# LED_Matrix.net
KiCad netlist of a schematic drawn in EAGLE
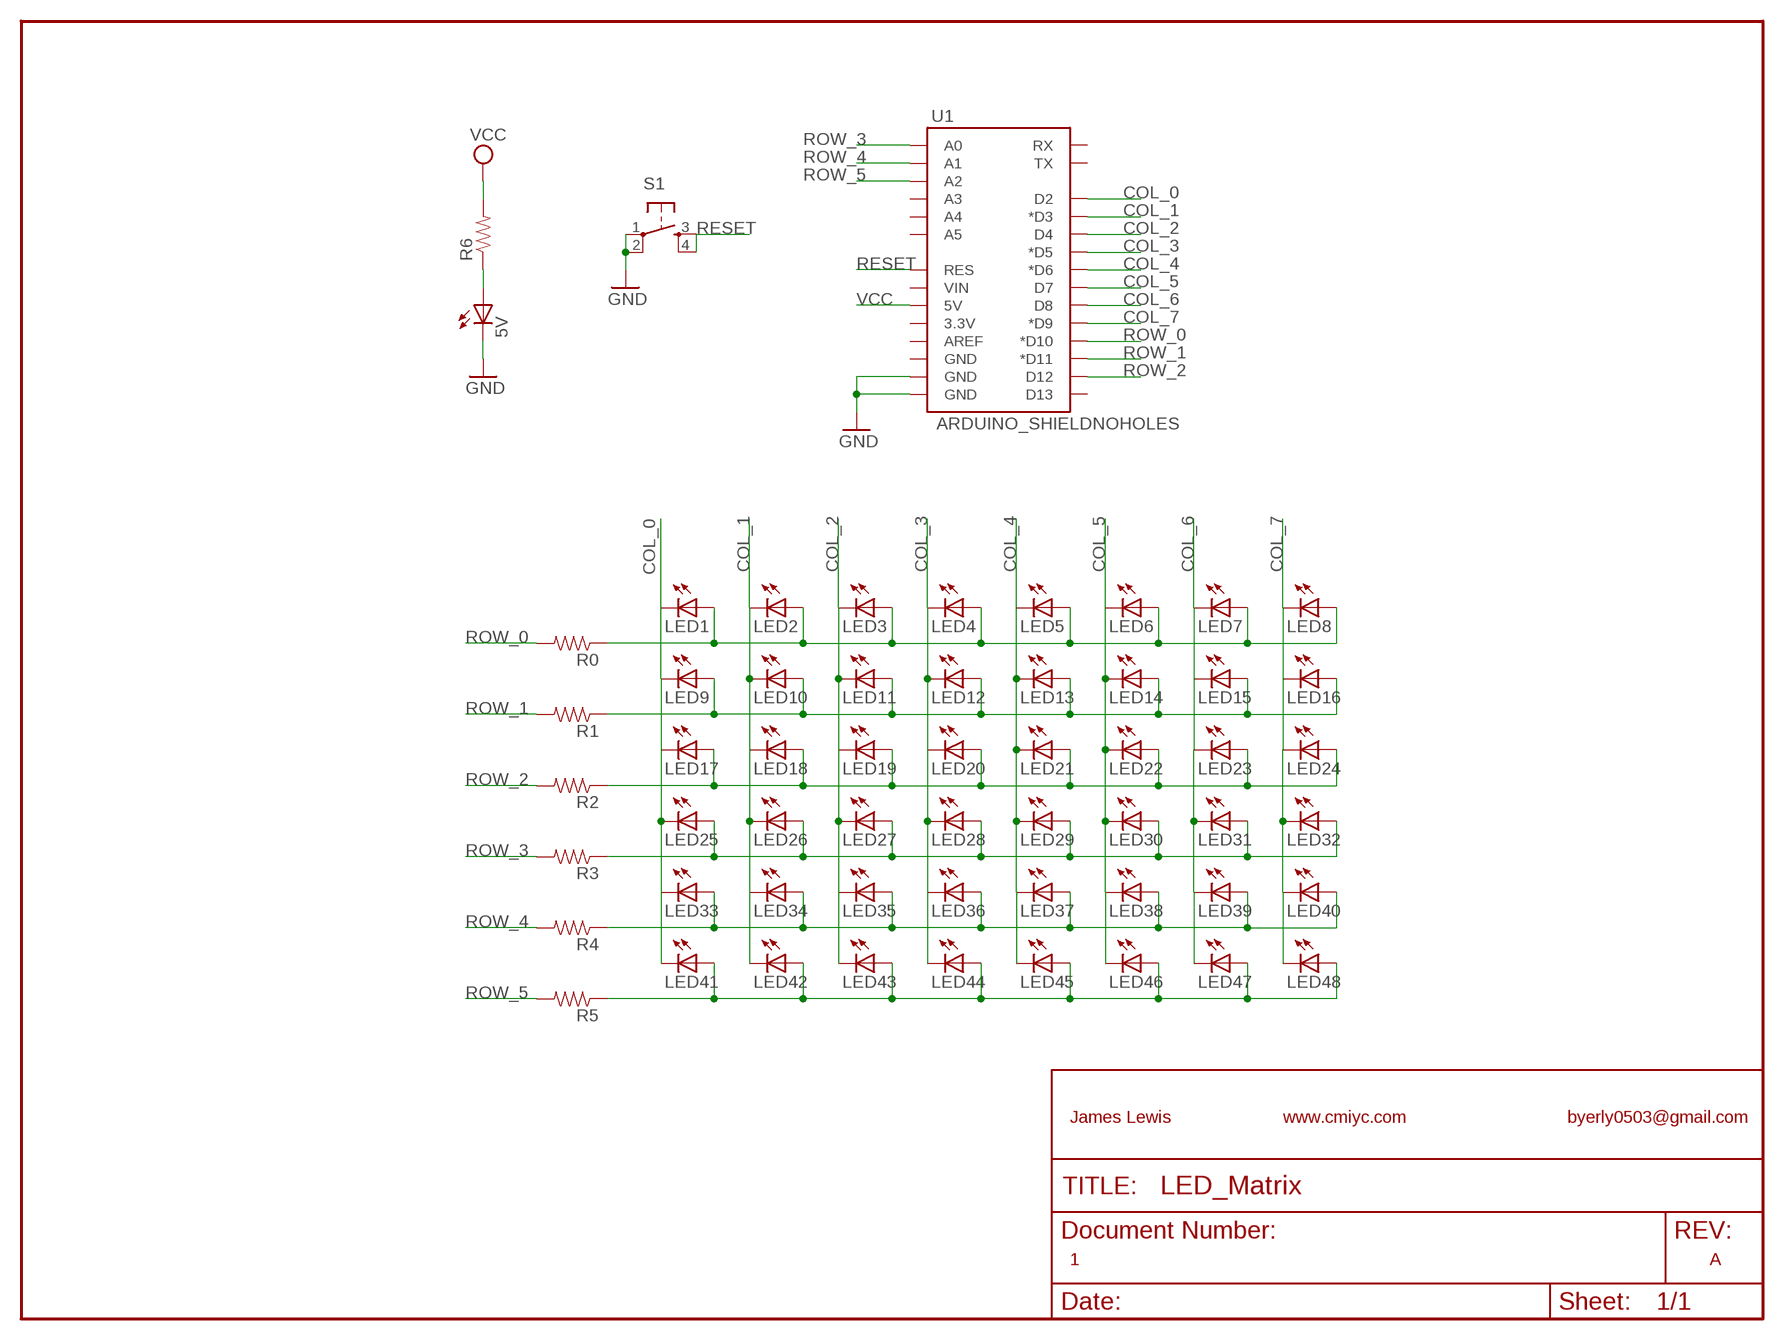
[diagram p0: schematic, sheet 1]

(export (version "E")
  (design (tool "Eeschema 10.0.6"))
  (components
    (comp (ref "5V")
      (value "LED1206")
      (footprint "eagle-import:LED-1206")
      (libsource (lib "eagle-import") (part "LED1206"))
    )
    (comp (ref "LED1")
      (value "LED5MM")
      (footprint "eagle-import:LED5MM")
      (libsource (lib "eagle-import") (part "LED5MM"))
    )
    (comp (ref "LED2")
      (value "LED5MM")
      (footprint "eagle-import:LED5MM")
      (libsource (lib "eagle-import") (part "LED5MM"))
    )
    (comp (ref "LED3")
      (value "LED5MM")
      (footprint "eagle-import:LED5MM")
      (libsource (lib "eagle-import") (part "LED5MM"))
    )
    (comp (ref "LED4")
      (value "LED5MM")
      (footprint "eagle-import:LED5MM")
      (libsource (lib "eagle-import") (part "LED5MM"))
    )
    (comp (ref "LED5")
      (value "LED5MM")
      (footprint "eagle-import:LED5MM")
      (libsource (lib "eagle-import") (part "LED5MM"))
    )
    (comp (ref "LED6")
      (value "LED5MM")
      (footprint "eagle-import:LED5MM")
      (libsource (lib "eagle-import") (part "LED5MM"))
    )
    (comp (ref "LED7")
      (value "LED5MM")
      (footprint "eagle-import:LED5MM")
      (libsource (lib "eagle-import") (part "LED5MM"))
    )
    (comp (ref "LED8")
      (value "LED5MM")
      (footprint "eagle-import:LED5MM")
      (libsource (lib "eagle-import") (part "LED5MM"))
    )
    (comp (ref "LED9")
      (value "LED5MM")
      (footprint "eagle-import:LED5MM")
      (libsource (lib "eagle-import") (part "LED5MM"))
    )
    (comp (ref "LED10")
      (value "LED5MM")
      (footprint "eagle-import:LED5MM")
      (libsource (lib "eagle-import") (part "LED5MM"))
    )
    (comp (ref "LED11")
      (value "LED5MM")
      (footprint "eagle-import:LED5MM")
      (libsource (lib "eagle-import") (part "LED5MM"))
    )
    (comp (ref "LED12")
      (value "LED5MM")
      (footprint "eagle-import:LED5MM")
      (libsource (lib "eagle-import") (part "LED5MM"))
    )
    (comp (ref "LED13")
      (value "LED5MM")
      (footprint "eagle-import:LED5MM")
      (libsource (lib "eagle-import") (part "LED5MM"))
    )
    (comp (ref "LED14")
      (value "LED5MM")
      (footprint "eagle-import:LED5MM")
      (libsource (lib "eagle-import") (part "LED5MM"))
    )
    (comp (ref "LED15")
      (value "LED5MM")
      (footprint "eagle-import:LED5MM")
      (libsource (lib "eagle-import") (part "LED5MM"))
    )
    (comp (ref "LED16")
      (value "LED5MM")
      (footprint "eagle-import:LED5MM")
      (libsource (lib "eagle-import") (part "LED5MM"))
    )
    (comp (ref "LED17")
      (value "LED5MM")
      (footprint "eagle-import:LED5MM")
      (libsource (lib "eagle-import") (part "LED5MM"))
    )
    (comp (ref "LED18")
      (value "LED5MM")
      (footprint "eagle-import:LED5MM")
      (libsource (lib "eagle-import") (part "LED5MM"))
    )
    (comp (ref "LED19")
      (value "LED5MM")
      (footprint "eagle-import:LED5MM")
      (libsource (lib "eagle-import") (part "LED5MM"))
    )
    (comp (ref "LED20")
      (value "LED5MM")
      (footprint "eagle-import:LED5MM")
      (libsource (lib "eagle-import") (part "LED5MM"))
    )
    (comp (ref "LED21")
      (value "LED5MM")
      (footprint "eagle-import:LED5MM")
      (libsource (lib "eagle-import") (part "LED5MM"))
    )
    (comp (ref "LED22")
      (value "LED5MM")
      (footprint "eagle-import:LED5MM")
      (libsource (lib "eagle-import") (part "LED5MM"))
    )
    (comp (ref "LED23")
      (value "LED5MM")
      (footprint "eagle-import:LED5MM")
      (libsource (lib "eagle-import") (part "LED5MM"))
    )
    (comp (ref "LED24")
      (value "LED5MM")
      (footprint "eagle-import:LED5MM")
      (libsource (lib "eagle-import") (part "LED5MM"))
    )
    (comp (ref "LED25")
      (value "LED5MM")
      (footprint "eagle-import:LED5MM")
      (libsource (lib "eagle-import") (part "LED5MM"))
    )
    (comp (ref "LED26")
      (value "LED5MM")
      (footprint "eagle-import:LED5MM")
      (libsource (lib "eagle-import") (part "LED5MM"))
    )
    (comp (ref "LED27")
      (value "LED5MM")
      (footprint "eagle-import:LED5MM")
      (libsource (lib "eagle-import") (part "LED5MM"))
    )
    (comp (ref "LED28")
      (value "LED5MM")
      (footprint "eagle-import:LED5MM")
      (libsource (lib "eagle-import") (part "LED5MM"))
    )
    (comp (ref "LED29")
      (value "LED5MM")
      (footprint "eagle-import:LED5MM")
      (libsource (lib "eagle-import") (part "LED5MM"))
    )
    (comp (ref "LED30")
      (value "LED5MM")
      (footprint "eagle-import:LED5MM")
      (libsource (lib "eagle-import") (part "LED5MM"))
    )
    (comp (ref "LED31")
      (value "LED5MM")
      (footprint "eagle-import:LED5MM")
      (libsource (lib "eagle-import") (part "LED5MM"))
    )
    (comp (ref "LED32")
      (value "LED5MM")
      (footprint "eagle-import:LED5MM")
      (libsource (lib "eagle-import") (part "LED5MM"))
    )
    (comp (ref "LED33")
      (value "LED5MM")
      (footprint "eagle-import:LED5MM")
      (libsource (lib "eagle-import") (part "LED5MM"))
    )
    (comp (ref "LED34")
      (value "LED5MM")
      (footprint "eagle-import:LED5MM")
      (libsource (lib "eagle-import") (part "LED5MM"))
    )
    (comp (ref "LED35")
      (value "LED5MM")
      (footprint "eagle-import:LED5MM")
      (libsource (lib "eagle-import") (part "LED5MM"))
    )
    (comp (ref "LED36")
      (value "LED5MM")
      (footprint "eagle-import:LED5MM")
      (libsource (lib "eagle-import") (part "LED5MM"))
    )
    (comp (ref "LED37")
      (value "LED5MM")
      (footprint "eagle-import:LED5MM")
      (libsource (lib "eagle-import") (part "LED5MM"))
    )
    (comp (ref "LED38")
      (value "LED5MM")
      (footprint "eagle-import:LED5MM")
      (libsource (lib "eagle-import") (part "LED5MM"))
    )
    (comp (ref "LED39")
      (value "LED5MM")
      (footprint "eagle-import:LED5MM")
      (libsource (lib "eagle-import") (part "LED5MM"))
    )
    (comp (ref "LED40")
      (value "LED5MM")
      (footprint "eagle-import:LED5MM")
      (libsource (lib "eagle-import") (part "LED5MM"))
    )
    (comp (ref "LED41")
      (value "LED5MM")
      (footprint "eagle-import:LED5MM")
      (libsource (lib "eagle-import") (part "LED5MM"))
    )
    (comp (ref "LED42")
      (value "LED5MM")
      (footprint "eagle-import:LED5MM")
      (libsource (lib "eagle-import") (part "LED5MM"))
    )
    (comp (ref "LED43")
      (value "LED5MM")
      (footprint "eagle-import:LED5MM")
      (libsource (lib "eagle-import") (part "LED5MM"))
    )
    (comp (ref "LED44")
      (value "LED5MM")
      (footprint "eagle-import:LED5MM")
      (libsource (lib "eagle-import") (part "LED5MM"))
    )
    (comp (ref "LED45")
      (value "LED5MM")
      (footprint "eagle-import:LED5MM")
      (libsource (lib "eagle-import") (part "LED5MM"))
    )
    (comp (ref "LED46")
      (value "LED5MM")
      (footprint "eagle-import:LED5MM")
      (libsource (lib "eagle-import") (part "LED5MM"))
    )
    (comp (ref "LED47")
      (value "LED5MM")
      (footprint "eagle-import:LED5MM")
      (libsource (lib "eagle-import") (part "LED5MM"))
    )
    (comp (ref "LED48")
      (value "LED5MM")
      (footprint "eagle-import:LED5MM")
      (libsource (lib "eagle-import") (part "LED5MM"))
    )
    (comp (ref "R0")
      (value "RESISTOR1206")
      (footprint "eagle-import:1206")
      (libsource (lib "eagle-import") (part "RESISTOR1206"))
    )
    (comp (ref "R1")
      (value "RESISTOR1206")
      (footprint "eagle-import:1206")
      (libsource (lib "eagle-import") (part "RESISTOR1206"))
    )
    (comp (ref "R2")
      (value "RESISTOR1206")
      (footprint "eagle-import:1206")
      (libsource (lib "eagle-import") (part "RESISTOR1206"))
    )
    (comp (ref "R3")
      (value "RESISTOR1206")
      (footprint "eagle-import:1206")
      (libsource (lib "eagle-import") (part "RESISTOR1206"))
    )
    (comp (ref "R4")
      (value "RESISTOR1206")
      (footprint "eagle-import:1206")
      (libsource (lib "eagle-import") (part "RESISTOR1206"))
    )
    (comp (ref "R5")
      (value "RESISTOR1206")
      (footprint "eagle-import:1206")
      (libsource (lib "eagle-import") (part "RESISTOR1206"))
    )
    (comp (ref "R6")
      (value "RESISTOR1206")
      (footprint "eagle-import:1206")
      (libsource (lib "eagle-import") (part "RESISTOR1206"))
    )
    (comp (ref "S1")
      (value "TAC_SWITCHSMD")
      (footprint "eagle-import:TACTILE_SWITCH_SMD")
      (libsource (lib "eagle-import") (part "TAC_SWITCHSMD"))
    )
    (comp (ref "U1")
      (value "ARDUINO_SHIELDNOHOLES")
      (footprint "eagle-import:DUEMILANOVE_SHIELD_NOHOLES")
      (libsource (lib "eagle-import") (part "ARDUINO_SHIELDNOHOLES"))
    )
  )
  (nets
    (net (code "1") (name "/COL_0") (class "Default")
      (node (ref "LED1") (pin "K") (pinfunction "C_K") (pintype "passive"))
      (node (ref "LED17") (pin "K") (pinfunction "C_K") (pintype "passive"))
      (node (ref "LED25") (pin "K") (pinfunction "C_K") (pintype "passive"))
      (node (ref "LED33") (pin "K") (pinfunction "C_K") (pintype "passive"))
      (node (ref "LED41") (pin "K") (pinfunction "C_K") (pintype "passive"))
      (node (ref "LED9") (pin "K") (pinfunction "C_K") (pintype "passive"))
      (node (ref "U1") (pin "D2") (pinfunction "D2_D2") (pintype "bidirectional"))
    )
    (net (code "2") (name "/COL_1") (class "Default")
      (node (ref "LED10") (pin "K") (pinfunction "C_K") (pintype "passive"))
      (node (ref "LED18") (pin "K") (pinfunction "C_K") (pintype "passive"))
      (node (ref "LED2") (pin "K") (pinfunction "C_K") (pintype "passive"))
      (node (ref "LED26") (pin "K") (pinfunction "C_K") (pintype "passive"))
      (node (ref "LED34") (pin "K") (pinfunction "C_K") (pintype "passive"))
      (node (ref "LED42") (pin "K") (pinfunction "C_K") (pintype "passive"))
      (node (ref "U1") (pin "D3") (pinfunction "*D3_D3") (pintype "bidirectional"))
    )
    (net (code "3") (name "/COL_2") (class "Default")
      (node (ref "LED11") (pin "K") (pinfunction "C_K") (pintype "passive"))
      (node (ref "LED19") (pin "K") (pinfunction "C_K") (pintype "passive"))
      (node (ref "LED27") (pin "K") (pinfunction "C_K") (pintype "passive"))
      (node (ref "LED3") (pin "K") (pinfunction "C_K") (pintype "passive"))
      (node (ref "LED35") (pin "K") (pinfunction "C_K") (pintype "passive"))
      (node (ref "LED43") (pin "K") (pinfunction "C_K") (pintype "passive"))
      (node (ref "U1") (pin "D4") (pinfunction "D4_D4") (pintype "bidirectional"))
    )
    (net (code "4") (name "/COL_3") (class "Default")
      (node (ref "LED12") (pin "K") (pinfunction "C_K") (pintype "passive"))
      (node (ref "LED20") (pin "K") (pinfunction "C_K") (pintype "passive"))
      (node (ref "LED28") (pin "K") (pinfunction "C_K") (pintype "passive"))
      (node (ref "LED36") (pin "K") (pinfunction "C_K") (pintype "passive"))
      (node (ref "LED4") (pin "K") (pinfunction "C_K") (pintype "passive"))
      (node (ref "LED44") (pin "K") (pinfunction "C_K") (pintype "passive"))
      (node (ref "U1") (pin "D5") (pinfunction "*D5_D5") (pintype "bidirectional"))
    )
    (net (code "5") (name "/COL_4") (class "Default")
      (node (ref "LED13") (pin "K") (pinfunction "C_K") (pintype "passive"))
      (node (ref "LED21") (pin "K") (pinfunction "C_K") (pintype "passive"))
      (node (ref "LED29") (pin "K") (pinfunction "C_K") (pintype "passive"))
      (node (ref "LED37") (pin "K") (pinfunction "C_K") (pintype "passive"))
      (node (ref "LED45") (pin "K") (pinfunction "C_K") (pintype "passive"))
      (node (ref "LED5") (pin "K") (pinfunction "C_K") (pintype "passive"))
      (node (ref "U1") (pin "D6") (pinfunction "*D6_D6") (pintype "bidirectional"))
    )
    (net (code "6") (name "/COL_5") (class "Default")
      (node (ref "LED14") (pin "K") (pinfunction "C_K") (pintype "passive"))
      (node (ref "LED22") (pin "K") (pinfunction "C_K") (pintype "passive"))
      (node (ref "LED30") (pin "K") (pinfunction "C_K") (pintype "passive"))
      (node (ref "LED38") (pin "K") (pinfunction "C_K") (pintype "passive"))
      (node (ref "LED46") (pin "K") (pinfunction "C_K") (pintype "passive"))
      (node (ref "LED6") (pin "K") (pinfunction "C_K") (pintype "passive"))
      (node (ref "U1") (pin "D7") (pinfunction "D7_D7") (pintype "bidirectional"))
    )
    (net (code "7") (name "/COL_6") (class "Default")
      (node (ref "LED15") (pin "K") (pinfunction "C_K") (pintype "passive"))
      (node (ref "LED23") (pin "K") (pinfunction "C_K") (pintype "passive"))
      (node (ref "LED31") (pin "K") (pinfunction "C_K") (pintype "passive"))
      (node (ref "LED39") (pin "K") (pinfunction "C_K") (pintype "passive"))
      (node (ref "LED47") (pin "K") (pinfunction "C_K") (pintype "passive"))
      (node (ref "LED7") (pin "K") (pinfunction "C_K") (pintype "passive"))
      (node (ref "U1") (pin "D8") (pinfunction "D8_D8") (pintype "bidirectional"))
    )
    (net (code "8") (name "/COL_7") (class "Default")
      (node (ref "LED16") (pin "K") (pinfunction "C_K") (pintype "passive"))
      (node (ref "LED24") (pin "K") (pinfunction "C_K") (pintype "passive"))
      (node (ref "LED32") (pin "K") (pinfunction "C_K") (pintype "passive"))
      (node (ref "LED40") (pin "K") (pinfunction "C_K") (pintype "passive"))
      (node (ref "LED48") (pin "K") (pinfunction "C_K") (pintype "passive"))
      (node (ref "LED8") (pin "K") (pinfunction "C_K") (pintype "passive"))
      (node (ref "U1") (pin "D9") (pinfunction "*D9_D9") (pintype "bidirectional"))
    )
    (net (code "9") (name "/RESET") (class "Default")
      (node (ref "S1") (pin "3") (pinfunction "3_3") (pintype "passive"))
      (node (ref "S1") (pin "4") (pinfunction "4_4") (pintype "passive"))
      (node (ref "U1") (pin "RES") (pinfunction "RES_RES") (pintype "bidirectional"))
    )
    (net (code "10") (name "/ROW_0") (class "Default")
      (node (ref "R0") (pin "2") (pinfunction "2_2") (pintype "passive"))
      (node (ref "U1") (pin "D10") (pinfunction "*D10_D10") (pintype "bidirectional"))
    )
    (net (code "11") (name "/ROW_1") (class "Default")
      (node (ref "R1") (pin "2") (pinfunction "2_2") (pintype "passive"))
      (node (ref "U1") (pin "D11") (pinfunction "*D11_D11") (pintype "bidirectional"))
    )
    (net (code "12") (name "/ROW_2") (class "Default")
      (node (ref "R2") (pin "2") (pinfunction "2_2") (pintype "passive"))
      (node (ref "U1") (pin "D12") (pinfunction "D12_D12") (pintype "bidirectional"))
    )
    (net (code "13") (name "/ROW_3") (class "Default")
      (node (ref "R3") (pin "2") (pinfunction "2_2") (pintype "passive"))
      (node (ref "U1") (pin "A0") (pinfunction "A0_A0") (pintype "bidirectional"))
    )
    (net (code "14") (name "/ROW_4") (class "Default")
      (node (ref "R4") (pin "2") (pinfunction "2_2") (pintype "passive"))
      (node (ref "U1") (pin "A1") (pinfunction "A1_A1") (pintype "bidirectional"))
    )
    (net (code "15") (name "/ROW_5") (class "Default")
      (node (ref "R5") (pin "2") (pinfunction "2_2") (pintype "passive"))
      (node (ref "U1") (pin "A2") (pinfunction "A2_A2") (pintype "bidirectional"))
    )
    (net (code "16") (name "GND") (class "Default")
      (node (ref "5V") (pin "C") (pinfunction "C_C") (pintype "passive"))
      (node (ref "S1") (pin "1") (pinfunction "1_1") (pintype "passive"))
      (node (ref "S1") (pin "2") (pinfunction "2_2") (pintype "passive"))
      (node (ref "U1") (pin "GND@0") (pinfunction "GND_GND@0") (pintype "bidirectional"))
      (node (ref "U1") (pin "GND@1") (pinfunction "GND_GND@1") (pintype "bidirectional"))
    )
    (net (code "17") (name "Net-(5V-PadA)") (class "Default")
      (node (ref "5V") (pin "A") (pinfunction "A_A") (pintype "passive"))
      (node (ref "R6") (pin "1") (pinfunction "1_1") (pintype "passive"))
    )
    (net (code "18") (name "Net-(LED1-PadA)") (class "Default")
      (node (ref "LED1") (pin "A") (pinfunction "A_A") (pintype "passive"))
      (node (ref "LED2") (pin "A") (pinfunction "A_A") (pintype "passive"))
      (node (ref "LED3") (pin "A") (pinfunction "A_A") (pintype "passive"))
      (node (ref "LED4") (pin "A") (pinfunction "A_A") (pintype "passive"))
      (node (ref "LED5") (pin "A") (pinfunction "A_A") (pintype "passive"))
      (node (ref "LED6") (pin "A") (pinfunction "A_A") (pintype "passive"))
      (node (ref "LED7") (pin "A") (pinfunction "A_A") (pintype "passive"))
      (node (ref "LED8") (pin "A") (pinfunction "A_A") (pintype "passive"))
      (node (ref "R0") (pin "1") (pinfunction "1_1") (pintype "passive"))
    )
    (net (code "19") (name "Net-(LED10-PadA)") (class "Default")
      (node (ref "LED10") (pin "A") (pinfunction "A_A") (pintype "passive"))
      (node (ref "LED11") (pin "A") (pinfunction "A_A") (pintype "passive"))
      (node (ref "LED12") (pin "A") (pinfunction "A_A") (pintype "passive"))
      (node (ref "LED13") (pin "A") (pinfunction "A_A") (pintype "passive"))
      (node (ref "LED14") (pin "A") (pinfunction "A_A") (pintype "passive"))
      (node (ref "LED15") (pin "A") (pinfunction "A_A") (pintype "passive"))
      (node (ref "LED16") (pin "A") (pinfunction "A_A") (pintype "passive"))
      (node (ref "LED9") (pin "A") (pinfunction "A_A") (pintype "passive"))
      (node (ref "R1") (pin "1") (pinfunction "1_1") (pintype "passive"))
    )
    (net (code "20") (name "Net-(LED17-PadA)") (class "Default")
      (node (ref "LED17") (pin "A") (pinfunction "A_A") (pintype "passive"))
      (node (ref "LED18") (pin "A") (pinfunction "A_A") (pintype "passive"))
      (node (ref "LED19") (pin "A") (pinfunction "A_A") (pintype "passive"))
      (node (ref "LED20") (pin "A") (pinfunction "A_A") (pintype "passive"))
      (node (ref "LED21") (pin "A") (pinfunction "A_A") (pintype "passive"))
      (node (ref "LED22") (pin "A") (pinfunction "A_A") (pintype "passive"))
      (node (ref "LED23") (pin "A") (pinfunction "A_A") (pintype "passive"))
      (node (ref "LED24") (pin "A") (pinfunction "A_A") (pintype "passive"))
      (node (ref "R2") (pin "1") (pinfunction "1_1") (pintype "passive"))
    )
    (net (code "21") (name "Net-(LED25-PadA)") (class "Default")
      (node (ref "LED25") (pin "A") (pinfunction "A_A") (pintype "passive"))
      (node (ref "LED26") (pin "A") (pinfunction "A_A") (pintype "passive"))
      (node (ref "LED27") (pin "A") (pinfunction "A_A") (pintype "passive"))
      (node (ref "LED28") (pin "A") (pinfunction "A_A") (pintype "passive"))
      (node (ref "LED29") (pin "A") (pinfunction "A_A") (pintype "passive"))
      (node (ref "LED30") (pin "A") (pinfunction "A_A") (pintype "passive"))
      (node (ref "LED31") (pin "A") (pinfunction "A_A") (pintype "passive"))
      (node (ref "LED32") (pin "A") (pinfunction "A_A") (pintype "passive"))
      (node (ref "R3") (pin "1") (pinfunction "1_1") (pintype "passive"))
    )
    (net (code "22") (name "Net-(LED33-PadA)") (class "Default")
      (node (ref "LED33") (pin "A") (pinfunction "A_A") (pintype "passive"))
      (node (ref "LED34") (pin "A") (pinfunction "A_A") (pintype "passive"))
      (node (ref "LED35") (pin "A") (pinfunction "A_A") (pintype "passive"))
      (node (ref "LED36") (pin "A") (pinfunction "A_A") (pintype "passive"))
      (node (ref "LED37") (pin "A") (pinfunction "A_A") (pintype "passive"))
      (node (ref "LED38") (pin "A") (pinfunction "A_A") (pintype "passive"))
      (node (ref "LED39") (pin "A") (pinfunction "A_A") (pintype "passive"))
      (node (ref "LED40") (pin "A") (pinfunction "A_A") (pintype "passive"))
      (node (ref "R4") (pin "1") (pinfunction "1_1") (pintype "passive"))
    )
    (net (code "23") (name "Net-(LED41-PadA)") (class "Default")
      (node (ref "LED41") (pin "A") (pinfunction "A_A") (pintype "passive"))
      (node (ref "LED42") (pin "A") (pinfunction "A_A") (pintype "passive"))
      (node (ref "LED43") (pin "A") (pinfunction "A_A") (pintype "passive"))
      (node (ref "LED44") (pin "A") (pinfunction "A_A") (pintype "passive"))
      (node (ref "LED45") (pin "A") (pinfunction "A_A") (pintype "passive"))
      (node (ref "LED46") (pin "A") (pinfunction "A_A") (pintype "passive"))
      (node (ref "LED47") (pin "A") (pinfunction "A_A") (pintype "passive"))
      (node (ref "LED48") (pin "A") (pinfunction "A_A") (pintype "passive"))
      (node (ref "R5") (pin "1") (pinfunction "1_1") (pintype "passive"))
    )
    (net (code "24") (name "VCC") (class "Default")
      (node (ref "R6") (pin "2") (pinfunction "2_2") (pintype "passive"))
      (node (ref "U1") (pin "5V") (pinfunction "5V_5V") (pintype "bidirectional"))
    )
    (net (code "25") (name "unconnected-(U1-GND-PadGND@2)") (class "Default")
      (node (ref "U1") (pin "GND@2") (pinfunction "GND_GND@2") (pintype "bidirectional"))
    )
    (net (code "26") (name "unconnected-(U1-Pad3.3V)") (class "Default")
      (node (ref "U1") (pin "3.3V") (pinfunction "3.3V_3.3V") (pintype "bidirectional"))
    )
    (net (code "27") (name "unconnected-(U1-PadA3)") (class "Default")
      (node (ref "U1") (pin "A3") (pinfunction "A3_A3") (pintype "bidirectional"))
    )
    (net (code "28") (name "unconnected-(U1-PadA4)") (class "Default")
      (node (ref "U1") (pin "A4") (pinfunction "A4_A4") (pintype "bidirectional"))
    )
    (net (code "29") (name "unconnected-(U1-PadA5)") (class "Default")
      (node (ref "U1") (pin "A5") (pinfunction "A5_A5") (pintype "bidirectional"))
    )
    (net (code "30") (name "unconnected-(U1-PadAREF)") (class "Default")
      (node (ref "U1") (pin "AREF") (pinfunction "AREF_AREF") (pintype "bidirectional"))
    )
    (net (code "31") (name "unconnected-(U1-PadD13)") (class "Default")
      (node (ref "U1") (pin "D13") (pinfunction "D13_D13") (pintype "bidirectional"))
    )
    (net (code "32") (name "unconnected-(U1-PadRX)") (class "Default")
      (node (ref "U1") (pin "RX") (pinfunction "RX_RX") (pintype "bidirectional"))
    )
    (net (code "33") (name "unconnected-(U1-PadTX)") (class "Default")
      (node (ref "U1") (pin "TX") (pinfunction "TX_TX") (pintype "bidirectional"))
    )
    (net (code "34") (name "unconnected-(U1-PadVIN)") (class "Default")
      (node (ref "U1") (pin "VIN") (pinfunction "VIN_VIN") (pintype "bidirectional"))
    )
  )
)
